# Interconnect_board_limit_switches_v1p4.net
KiCad netlist of a schematic drawn in EAGLE
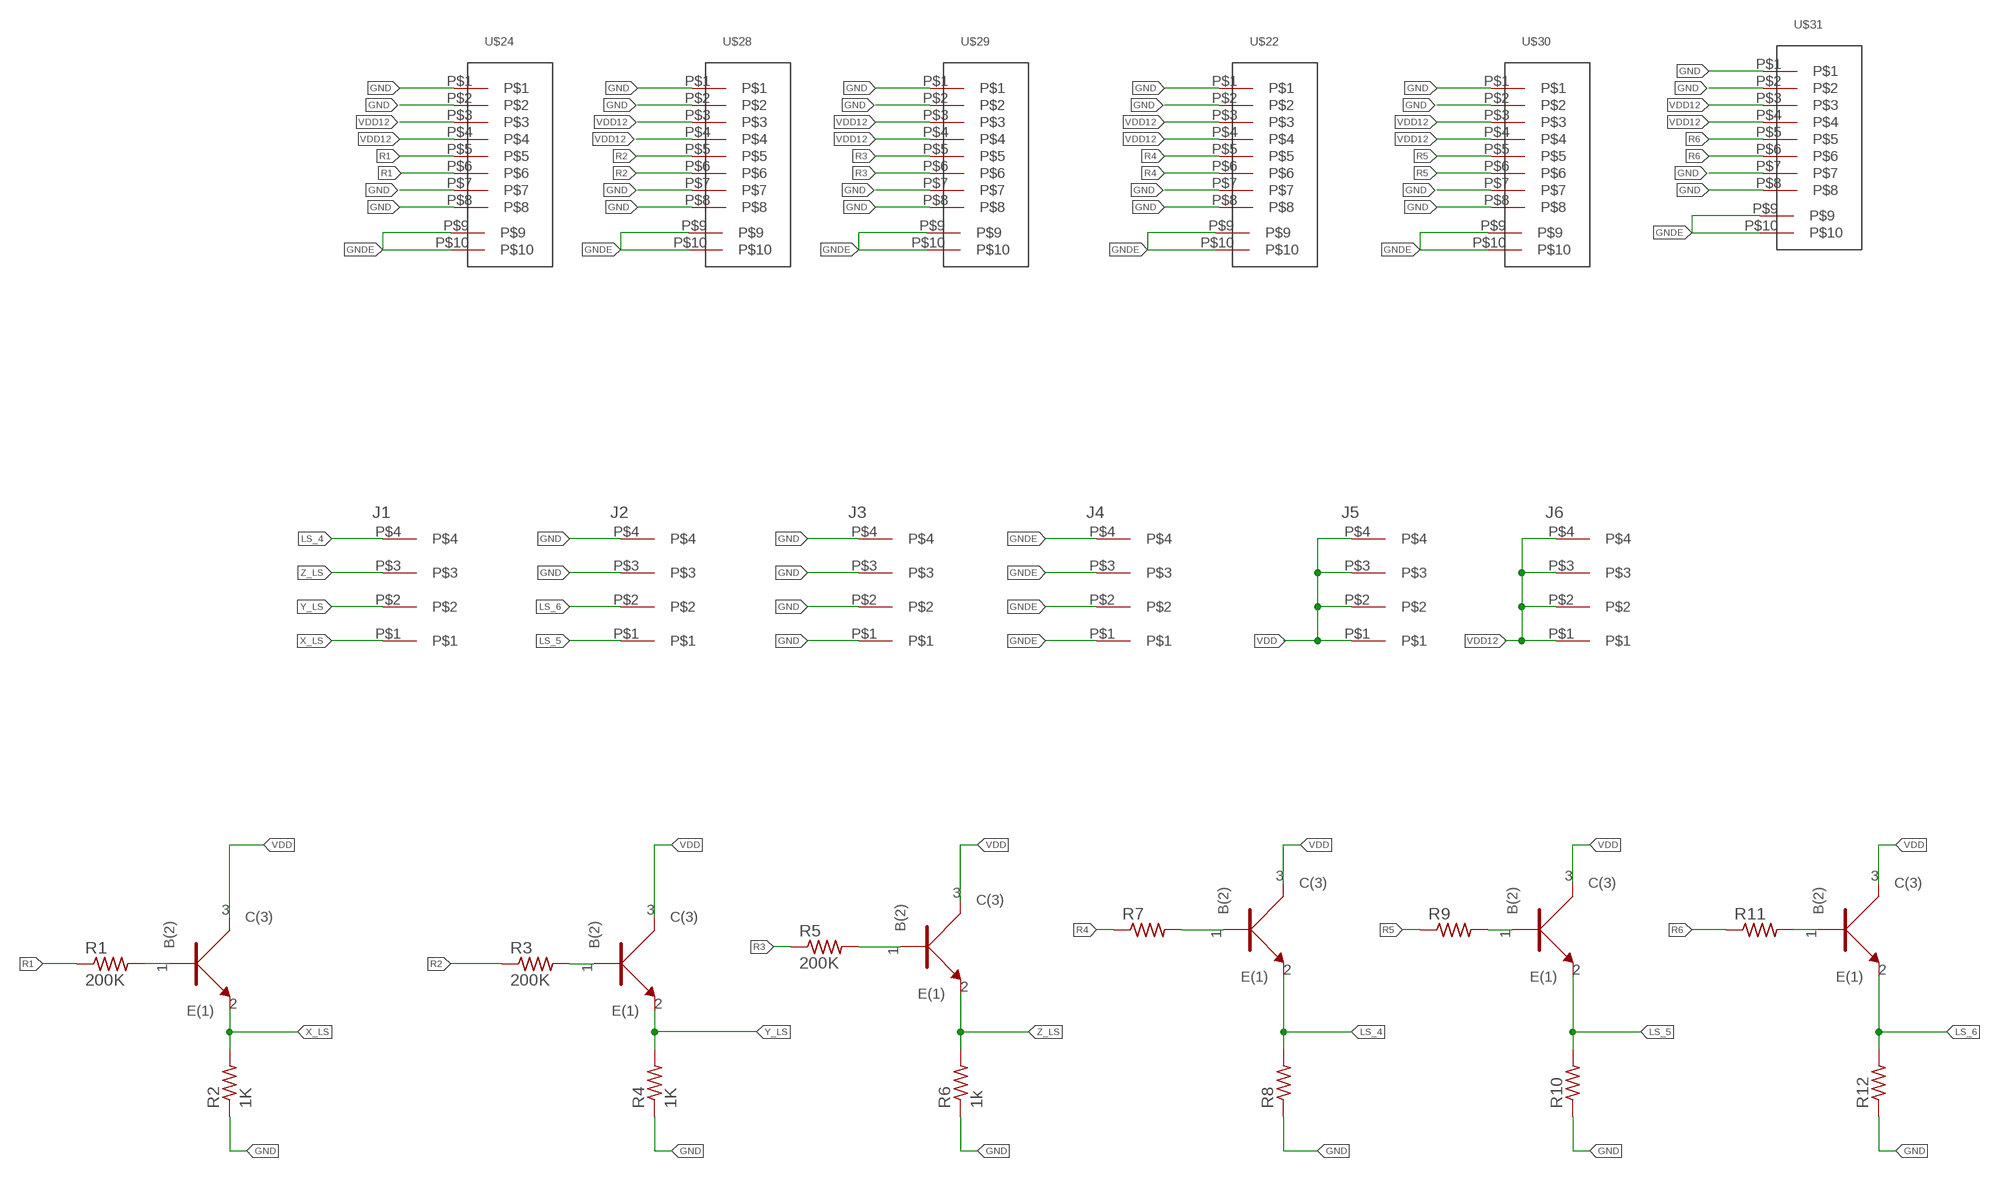
[diagram p0: schematic, sheet 1]

(export (version "E")
  (design (tool "Eeschema 10.0.6"))
  (components
    (comp (ref "J1")
      (value "3.81MM_1_X_4_RT_ANGLE_PLUG_HEADER")
      (footprint "eagle-import:1X4_3.81MM_PITCH")
      (libsource (lib "eagle-import") (part "3.81MM_1_X_4_RT_ANGLE_PLUG_HEADER"))
    )
    (comp (ref "J2")
      (value "3.81MM_1_X_4_RT_ANGLE_PLUG_HEADER")
      (footprint "eagle-import:1X4_3.81MM_PITCH")
      (libsource (lib "eagle-import") (part "3.81MM_1_X_4_RT_ANGLE_PLUG_HEADER"))
    )
    (comp (ref "J3")
      (value "3.81MM_1_X_4_RT_ANGLE_PLUG_HEADER")
      (footprint "eagle-import:1X4_3.81MM_PITCH")
      (libsource (lib "eagle-import") (part "3.81MM_1_X_4_RT_ANGLE_PLUG_HEADER"))
    )
    (comp (ref "J4")
      (value "3.81MM_1_X_4_RT_ANGLE_PLUG_HEADER")
      (footprint "eagle-import:1X4_3.81MM_PITCH")
      (libsource (lib "eagle-import") (part "3.81MM_1_X_4_RT_ANGLE_PLUG_HEADER"))
    )
    (comp (ref "J5")
      (value "3.81MM_1_X_4_RT_ANGLE_PLUG_HEADER")
      (footprint "eagle-import:1X4_3.81MM_PITCH")
      (libsource (lib "eagle-import") (part "3.81MM_1_X_4_RT_ANGLE_PLUG_HEADER"))
    )
    (comp (ref "J6")
      (value "3.81MM_1_X_4_RT_ANGLE_PLUG_HEADER")
      (footprint "eagle-import:1X4_3.81MM_PITCH")
      (libsource (lib "eagle-import") (part "3.81MM_1_X_4_RT_ANGLE_PLUG_HEADER"))
    )
    (comp (ref "R1")
      (value "200K")
      (footprint "eagle-import:0805")
      (libsource (lib "eagle-import") (part "R_0805"))
    )
    (comp (ref "R2")
      (value "1K")
      (footprint "eagle-import:0805")
      (libsource (lib "eagle-import") (part "R_0805"))
    )
    (comp (ref "R3")
      (value "200K")
      (footprint "eagle-import:0805")
      (libsource (lib "eagle-import") (part "R_0805"))
    )
    (comp (ref "R4")
      (value "1K")
      (footprint "eagle-import:0805")
      (libsource (lib "eagle-import") (part "R_0805"))
    )
    (comp (ref "R5")
      (value "200K")
      (footprint "eagle-import:0805")
      (libsource (lib "eagle-import") (part "R_0805"))
    )
    (comp (ref "R6")
      (value "1k")
      (footprint "eagle-import:0805")
      (libsource (lib "eagle-import") (part "R_0805"))
    )
    (comp (ref "R7")
      (value "R_0805")
      (footprint "eagle-import:0805")
      (libsource (lib "eagle-import") (part "R_0805"))
    )
    (comp (ref "R8")
      (value "R_0805")
      (footprint "eagle-import:0805")
      (libsource (lib "eagle-import") (part "R_0805"))
    )
    (comp (ref "R9")
      (value "R_0805")
      (footprint "eagle-import:0805")
      (libsource (lib "eagle-import") (part "R_0805"))
    )
    (comp (ref "R10")
      (value "R_0805")
      (footprint "eagle-import:0805")
      (libsource (lib "eagle-import") (part "R_0805"))
    )
    (comp (ref "R11")
      (value "R_0805")
      (footprint "eagle-import:0805")
      (libsource (lib "eagle-import") (part "R_0805"))
    )
    (comp (ref "R12")
      (value "R_0805")
      (footprint "eagle-import:0805")
      (libsource (lib "eagle-import") (part "R_0805"))
    )
    (comp (ref "U$22")
      (value "RJ45_SMTRJ")
      (footprint "eagle-import:RJ45_SMT")
      (libsource (lib "eagle-import") (part "RJ45_SMTRJ"))
    )
    (comp (ref "U$24")
      (value "RJ45_SMTRJ")
      (footprint "eagle-import:RJ45_SMT")
      (libsource (lib "eagle-import") (part "RJ45_SMTRJ"))
    )
    (comp (ref "U$28")
      (value "RJ45_SMTRJ")
      (footprint "eagle-import:RJ45_SMT")
      (libsource (lib "eagle-import") (part "RJ45_SMTRJ"))
    )
    (comp (ref "U$29")
      (value "RJ45_SMTRJ")
      (footprint "eagle-import:RJ45_SMT")
      (libsource (lib "eagle-import") (part "RJ45_SMTRJ"))
    )
    (comp (ref "U$30")
      (value "RJ45_SMTRJ")
      (footprint "eagle-import:RJ45_SMT")
      (libsource (lib "eagle-import") (part "RJ45_SMTRJ"))
    )
    (comp (ref "U$31")
      (value "RJ45_SMTRJ")
      (footprint "eagle-import:RJ45_SMT")
      (libsource (lib "eagle-import") (part "RJ45_SMTRJ"))
    )
    (comp (ref "U1")
      (value "BC846BW")
      (footprint "eagle-import:SOT323")
      (libsource (lib "eagle-import") (part "BC846BW"))
    )
    (comp (ref "U2")
      (value "BC846BW")
      (footprint "eagle-import:SOT323")
      (libsource (lib "eagle-import") (part "BC846BW"))
    )
    (comp (ref "U3")
      (value "BC846BW")
      (footprint "eagle-import:SOT323")
      (libsource (lib "eagle-import") (part "BC846BW"))
    )
    (comp (ref "U4")
      (value "BC846BW")
      (footprint "eagle-import:SOT323")
      (libsource (lib "eagle-import") (part "BC846BW"))
    )
    (comp (ref "U5")
      (value "BC846BW")
      (footprint "eagle-import:SOT323")
      (libsource (lib "eagle-import") (part "BC846BW"))
    )
    (comp (ref "U6")
      (value "BC846BW")
      (footprint "eagle-import:SOT323")
      (libsource (lib "eagle-import") (part "BC846BW"))
    )
  )
  (nets
    (net (code "1") (name "GND") (class "Default")
      (node (ref "J2") (pin "P$3") (pinfunction "P$3_P$3") (pintype "bidirectional"))
      (node (ref "J2") (pin "P$4") (pinfunction "P$4_P$4") (pintype "bidirectional"))
      (node (ref "J3") (pin "P$1") (pinfunction "P$1_P$1") (pintype "bidirectional"))
      (node (ref "J3") (pin "P$2") (pinfunction "P$2_P$2") (pintype "bidirectional"))
      (node (ref "J3") (pin "P$3") (pinfunction "P$3_P$3") (pintype "bidirectional"))
      (node (ref "J3") (pin "P$4") (pinfunction "P$4_P$4") (pintype "bidirectional"))
      (node (ref "R10") (pin "1") (pinfunction "1_1") (pintype "passive"))
      (node (ref "R12") (pin "1") (pinfunction "1_1") (pintype "passive"))
      (node (ref "R2") (pin "1") (pinfunction "1_1") (pintype "passive"))
      (node (ref "R4") (pin "1") (pinfunction "1_1") (pintype "passive"))
      (node (ref "R6") (pin "1") (pinfunction "1_1") (pintype "passive"))
      (node (ref "R8") (pin "1") (pinfunction "1_1") (pintype "passive"))
      (node (ref "U$22") (pin "P$1") (pinfunction "P$1_P$1") (pintype "bidirectional"))
      (node (ref "U$22") (pin "P$2") (pinfunction "P$2_P$2") (pintype "bidirectional"))
      (node (ref "U$22") (pin "P$7") (pinfunction "P$7_P$7") (pintype "bidirectional"))
      (node (ref "U$22") (pin "P$8") (pinfunction "P$8_P$8") (pintype "bidirectional"))
      (node (ref "U$24") (pin "P$1") (pinfunction "P$1_P$1") (pintype "bidirectional"))
      (node (ref "U$24") (pin "P$2") (pinfunction "P$2_P$2") (pintype "bidirectional"))
      (node (ref "U$24") (pin "P$7") (pinfunction "P$7_P$7") (pintype "bidirectional"))
      (node (ref "U$24") (pin "P$8") (pinfunction "P$8_P$8") (pintype "bidirectional"))
      (node (ref "U$28") (pin "P$1") (pinfunction "P$1_P$1") (pintype "bidirectional"))
      (node (ref "U$28") (pin "P$2") (pinfunction "P$2_P$2") (pintype "bidirectional"))
      (node (ref "U$28") (pin "P$7") (pinfunction "P$7_P$7") (pintype "bidirectional"))
      (node (ref "U$28") (pin "P$8") (pinfunction "P$8_P$8") (pintype "bidirectional"))
      (node (ref "U$29") (pin "P$1") (pinfunction "P$1_P$1") (pintype "bidirectional"))
      (node (ref "U$29") (pin "P$2") (pinfunction "P$2_P$2") (pintype "bidirectional"))
      (node (ref "U$29") (pin "P$7") (pinfunction "P$7_P$7") (pintype "bidirectional"))
      (node (ref "U$29") (pin "P$8") (pinfunction "P$8_P$8") (pintype "bidirectional"))
      (node (ref "U$30") (pin "P$1") (pinfunction "P$1_P$1") (pintype "bidirectional"))
      (node (ref "U$30") (pin "P$2") (pinfunction "P$2_P$2") (pintype "bidirectional"))
      (node (ref "U$30") (pin "P$7") (pinfunction "P$7_P$7") (pintype "bidirectional"))
      (node (ref "U$30") (pin "P$8") (pinfunction "P$8_P$8") (pintype "bidirectional"))
      (node (ref "U$31") (pin "P$1") (pinfunction "P$1_P$1") (pintype "bidirectional"))
      (node (ref "U$31") (pin "P$2") (pinfunction "P$2_P$2") (pintype "bidirectional"))
      (node (ref "U$31") (pin "P$7") (pinfunction "P$7_P$7") (pintype "bidirectional"))
      (node (ref "U$31") (pin "P$8") (pinfunction "P$8_P$8") (pintype "bidirectional"))
    )
    (net (code "2") (name "GNDE") (class "Default")
      (node (ref "J4") (pin "P$1") (pinfunction "P$1_P$1") (pintype "bidirectional"))
      (node (ref "J4") (pin "P$2") (pinfunction "P$2_P$2") (pintype "bidirectional"))
      (node (ref "J4") (pin "P$3") (pinfunction "P$3_P$3") (pintype "bidirectional"))
      (node (ref "J4") (pin "P$4") (pinfunction "P$4_P$4") (pintype "bidirectional"))
      (node (ref "U$22") (pin "P$10") (pinfunction "P$10_P$10") (pintype "bidirectional"))
      (node (ref "U$22") (pin "P$9") (pinfunction "P$9_P$9") (pintype "bidirectional"))
      (node (ref "U$24") (pin "P$10") (pinfunction "P$10_P$10") (pintype "bidirectional"))
      (node (ref "U$24") (pin "P$9") (pinfunction "P$9_P$9") (pintype "bidirectional"))
      (node (ref "U$28") (pin "P$10") (pinfunction "P$10_P$10") (pintype "bidirectional"))
      (node (ref "U$28") (pin "P$9") (pinfunction "P$9_P$9") (pintype "bidirectional"))
      (node (ref "U$29") (pin "P$10") (pinfunction "P$10_P$10") (pintype "bidirectional"))
      (node (ref "U$29") (pin "P$9") (pinfunction "P$9_P$9") (pintype "bidirectional"))
      (node (ref "U$30") (pin "P$10") (pinfunction "P$10_P$10") (pintype "bidirectional"))
      (node (ref "U$30") (pin "P$9") (pinfunction "P$9_P$9") (pintype "bidirectional"))
      (node (ref "U$31") (pin "P$10") (pinfunction "P$10_P$10") (pintype "bidirectional"))
      (node (ref "U$31") (pin "P$9") (pinfunction "P$9_P$9") (pintype "bidirectional"))
    )
    (net (code "3") (name "LS_4") (class "Default")
      (node (ref "J1") (pin "P$4") (pinfunction "P$4_P$4") (pintype "bidirectional"))
      (node (ref "R8") (pin "2") (pinfunction "2_2") (pintype "passive"))
      (node (ref "U4") (pin "2") (pinfunction "E(1)_2") (pintype "output"))
    )
    (net (code "4") (name "LS_5") (class "Default")
      (node (ref "J2") (pin "P$1") (pinfunction "P$1_P$1") (pintype "bidirectional"))
      (node (ref "R10") (pin "2") (pinfunction "2_2") (pintype "passive"))
      (node (ref "U5") (pin "2") (pinfunction "E(1)_2") (pintype "output"))
    )
    (net (code "5") (name "LS_6") (class "Default")
      (node (ref "J2") (pin "P$2") (pinfunction "P$2_P$2") (pintype "bidirectional"))
      (node (ref "R12") (pin "2") (pinfunction "2_2") (pintype "passive"))
      (node (ref "U6") (pin "2") (pinfunction "E(1)_2") (pintype "output"))
    )
    (net (code "6") (name "Net-(U1-B(2))") (class "Default")
      (node (ref "R1") (pin "2") (pinfunction "2_2") (pintype "passive"))
      (node (ref "U1") (pin "1") (pinfunction "B(2)_1") (pintype "input"))
    )
    (net (code "7") (name "Net-(U2-B(2))") (class "Default")
      (node (ref "R3") (pin "2") (pinfunction "2_2") (pintype "passive"))
      (node (ref "U2") (pin "1") (pinfunction "B(2)_1") (pintype "input"))
    )
    (net (code "8") (name "Net-(U3-B(2))") (class "Default")
      (node (ref "R5") (pin "2") (pinfunction "2_2") (pintype "passive"))
      (node (ref "U3") (pin "1") (pinfunction "B(2)_1") (pintype "input"))
    )
    (net (code "9") (name "Net-(U4-B(2))") (class "Default")
      (node (ref "R7") (pin "2") (pinfunction "2_2") (pintype "passive"))
      (node (ref "U4") (pin "1") (pinfunction "B(2)_1") (pintype "input"))
    )
    (net (code "10") (name "Net-(U5-B(2))") (class "Default")
      (node (ref "R9") (pin "2") (pinfunction "2_2") (pintype "passive"))
      (node (ref "U5") (pin "1") (pinfunction "B(2)_1") (pintype "input"))
    )
    (net (code "11") (name "Net-(U6-B(2))") (class "Default")
      (node (ref "R11") (pin "2") (pinfunction "2_2") (pintype "passive"))
      (node (ref "U6") (pin "1") (pinfunction "B(2)_1") (pintype "input"))
    )
    (net (code "12") (name "R1") (class "Default")
      (node (ref "R1") (pin "1") (pinfunction "1_1") (pintype "passive"))
      (node (ref "U$24") (pin "P$5") (pinfunction "P$5_P$5") (pintype "bidirectional"))
      (node (ref "U$24") (pin "P$6") (pinfunction "P$6_P$6") (pintype "bidirectional"))
    )
    (net (code "13") (name "R2") (class "Default")
      (node (ref "R3") (pin "1") (pinfunction "1_1") (pintype "passive"))
      (node (ref "U$28") (pin "P$5") (pinfunction "P$5_P$5") (pintype "bidirectional"))
      (node (ref "U$28") (pin "P$6") (pinfunction "P$6_P$6") (pintype "bidirectional"))
    )
    (net (code "14") (name "R3") (class "Default")
      (node (ref "R5") (pin "1") (pinfunction "1_1") (pintype "passive"))
      (node (ref "U$29") (pin "P$5") (pinfunction "P$5_P$5") (pintype "bidirectional"))
      (node (ref "U$29") (pin "P$6") (pinfunction "P$6_P$6") (pintype "bidirectional"))
    )
    (net (code "15") (name "R4") (class "Default")
      (node (ref "R7") (pin "1") (pinfunction "1_1") (pintype "passive"))
      (node (ref "U$22") (pin "P$5") (pinfunction "P$5_P$5") (pintype "bidirectional"))
      (node (ref "U$22") (pin "P$6") (pinfunction "P$6_P$6") (pintype "bidirectional"))
    )
    (net (code "16") (name "R5") (class "Default")
      (node (ref "R9") (pin "1") (pinfunction "1_1") (pintype "passive"))
      (node (ref "U$30") (pin "P$5") (pinfunction "P$5_P$5") (pintype "bidirectional"))
      (node (ref "U$30") (pin "P$6") (pinfunction "P$6_P$6") (pintype "bidirectional"))
    )
    (net (code "17") (name "R6") (class "Default")
      (node (ref "R11") (pin "1") (pinfunction "1_1") (pintype "passive"))
      (node (ref "U$31") (pin "P$5") (pinfunction "P$5_P$5") (pintype "bidirectional"))
      (node (ref "U$31") (pin "P$6") (pinfunction "P$6_P$6") (pintype "bidirectional"))
    )
    (net (code "18") (name "VDD") (class "Default")
      (node (ref "J5") (pin "P$1") (pinfunction "P$1_P$1") (pintype "bidirectional"))
      (node (ref "J5") (pin "P$2") (pinfunction "P$2_P$2") (pintype "bidirectional"))
      (node (ref "J5") (pin "P$3") (pinfunction "P$3_P$3") (pintype "bidirectional"))
      (node (ref "J5") (pin "P$4") (pinfunction "P$4_P$4") (pintype "bidirectional"))
      (node (ref "U1") (pin "3") (pinfunction "C(3)_3") (pintype "input"))
      (node (ref "U2") (pin "3") (pinfunction "C(3)_3") (pintype "input"))
      (node (ref "U3") (pin "3") (pinfunction "C(3)_3") (pintype "input"))
      (node (ref "U4") (pin "3") (pinfunction "C(3)_3") (pintype "input"))
      (node (ref "U5") (pin "3") (pinfunction "C(3)_3") (pintype "input"))
      (node (ref "U6") (pin "3") (pinfunction "C(3)_3") (pintype "input"))
    )
    (net (code "19") (name "VDD12") (class "Default")
      (node (ref "J6") (pin "P$1") (pinfunction "P$1_P$1") (pintype "bidirectional"))
      (node (ref "J6") (pin "P$2") (pinfunction "P$2_P$2") (pintype "bidirectional"))
      (node (ref "J6") (pin "P$3") (pinfunction "P$3_P$3") (pintype "bidirectional"))
      (node (ref "J6") (pin "P$4") (pinfunction "P$4_P$4") (pintype "bidirectional"))
      (node (ref "U$22") (pin "P$3") (pinfunction "P$3_P$3") (pintype "bidirectional"))
      (node (ref "U$22") (pin "P$4") (pinfunction "P$4_P$4") (pintype "bidirectional"))
      (node (ref "U$24") (pin "P$3") (pinfunction "P$3_P$3") (pintype "bidirectional"))
      (node (ref "U$24") (pin "P$4") (pinfunction "P$4_P$4") (pintype "bidirectional"))
      (node (ref "U$28") (pin "P$3") (pinfunction "P$3_P$3") (pintype "bidirectional"))
      (node (ref "U$28") (pin "P$4") (pinfunction "P$4_P$4") (pintype "bidirectional"))
      (node (ref "U$29") (pin "P$3") (pinfunction "P$3_P$3") (pintype "bidirectional"))
      (node (ref "U$29") (pin "P$4") (pinfunction "P$4_P$4") (pintype "bidirectional"))
      (node (ref "U$30") (pin "P$3") (pinfunction "P$3_P$3") (pintype "bidirectional"))
      (node (ref "U$30") (pin "P$4") (pinfunction "P$4_P$4") (pintype "bidirectional"))
      (node (ref "U$31") (pin "P$3") (pinfunction "P$3_P$3") (pintype "bidirectional"))
      (node (ref "U$31") (pin "P$4") (pinfunction "P$4_P$4") (pintype "bidirectional"))
    )
    (net (code "20") (name "X_LS") (class "Default")
      (node (ref "J1") (pin "P$1") (pinfunction "P$1_P$1") (pintype "bidirectional"))
      (node (ref "R2") (pin "2") (pinfunction "2_2") (pintype "passive"))
      (node (ref "U1") (pin "2") (pinfunction "E(1)_2") (pintype "output"))
    )
    (net (code "21") (name "Y_LS") (class "Default")
      (node (ref "J1") (pin "P$2") (pinfunction "P$2_P$2") (pintype "bidirectional"))
      (node (ref "R4") (pin "2") (pinfunction "2_2") (pintype "passive"))
      (node (ref "U2") (pin "2") (pinfunction "E(1)_2") (pintype "output"))
    )
    (net (code "22") (name "Z_LS") (class "Default")
      (node (ref "J1") (pin "P$3") (pinfunction "P$3_P$3") (pintype "bidirectional"))
      (node (ref "R6") (pin "2") (pinfunction "2_2") (pintype "passive"))
      (node (ref "U3") (pin "2") (pinfunction "E(1)_2") (pintype "output"))
    )
  )
)
